# christmas-garland_easyeda.net
KiCad netlist of a schematic drawn in EasyEDA
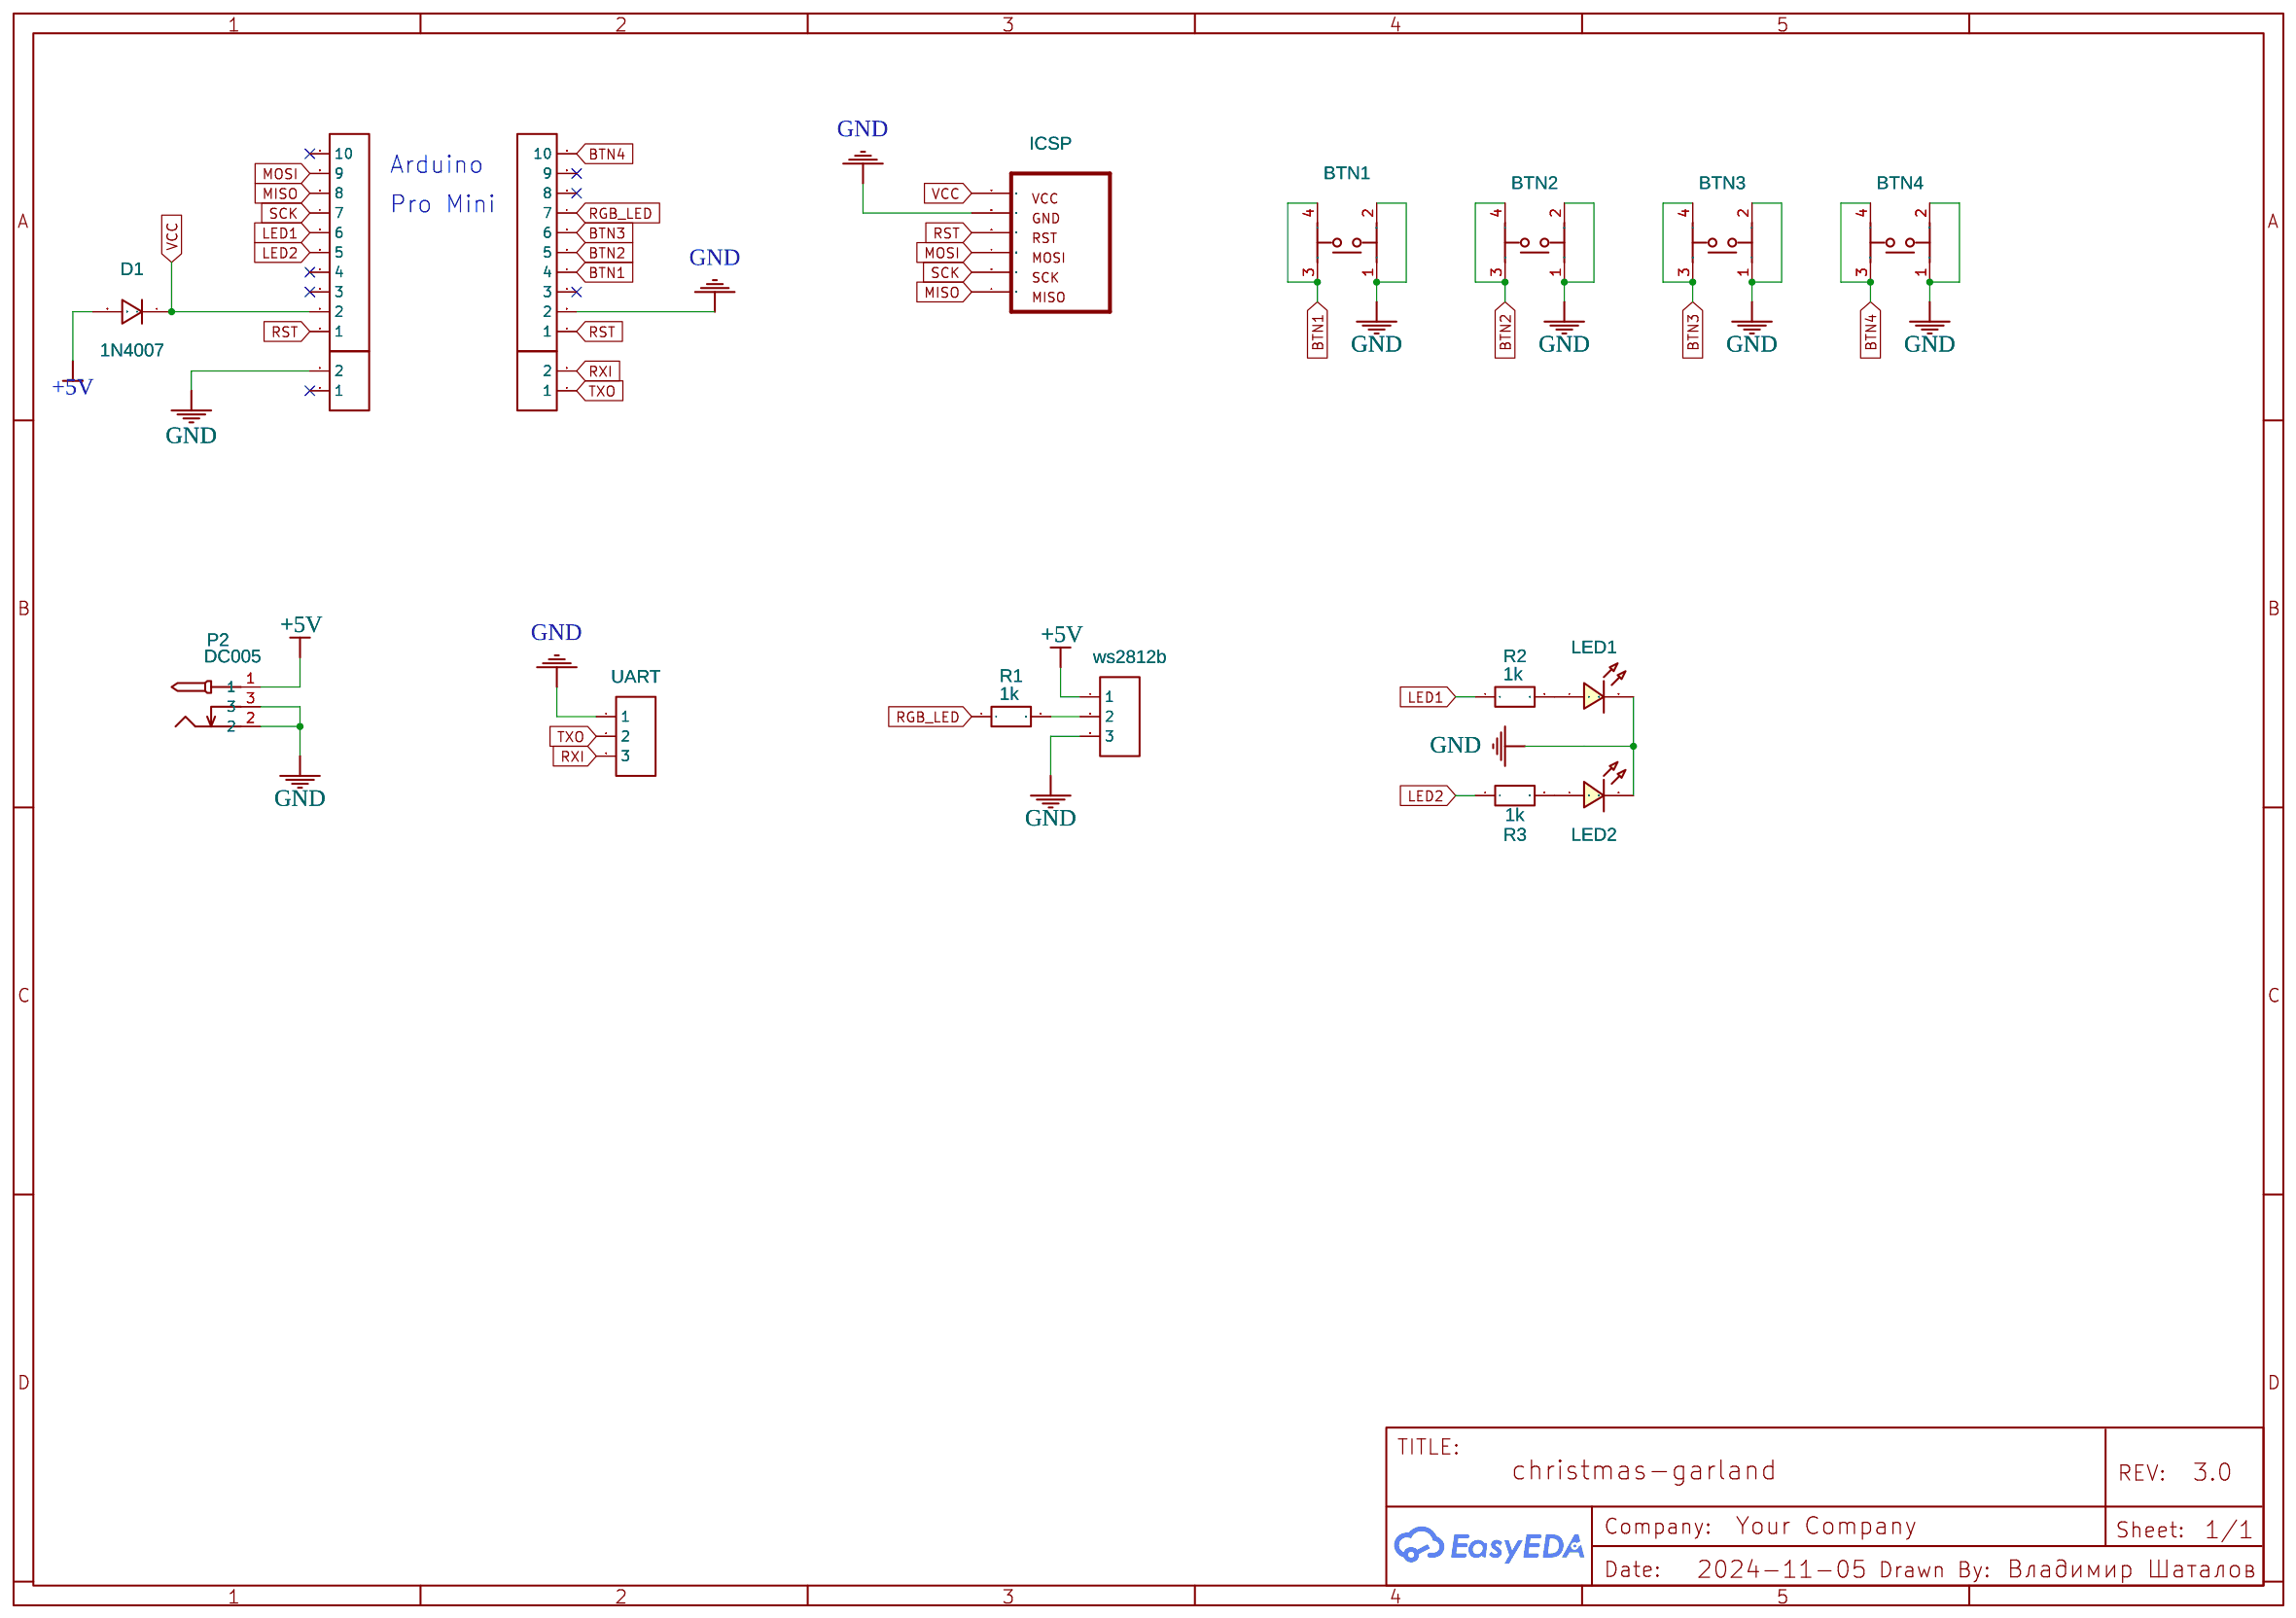
[diagram p0: schematic sheet]

(export (version "E")
  (design (tool "Eeschema 10.0.6"))
  (components
    (comp (ref "BTN1")
      (value "Reset")
      (fields (field (name "Manufacturer Part") "TS-1102-5016") (field (name "Manufacturer") "SOFNG"))
      (libsource (lib "") (part "SWITCH-6X6-5.08X7.62"))
    )
    (comp (ref "BTN2")
      (value "Reset")
      (fields (field (name "Manufacturer Part") "TS-1102-5016") (field (name "Manufacturer") "SOFNG"))
      (libsource (lib "") (part "SWITCH-6X6-5.08X7.62"))
    )
    (comp (ref "BTN3")
      (value "Reset")
      (fields (field (name "Manufacturer Part") "TS-1102-5016") (field (name "Manufacturer") "SOFNG"))
      (libsource (lib "") (part "SWITCH-6X6-5.08X7.62"))
    )
    (comp (ref "BTN4")
      (value "Reset")
      (fields (field (name "Manufacturer Part") "TS-1102-5016") (field (name "Manufacturer") "SOFNG"))
      (libsource (lib "") (part "SWITCH-6X6-5.08X7.62"))
    )
    (comp (ref "D1")
      (value "1N4007")
      (fields (field (name "Manufacturer Part") "1N4007W") (field (name "Manufacturer") "BLUE ROCKET"))
      (libsource (lib "") (part "1N4007W"))
    )
    (comp (ref "H1") (value "ws2812b") (libsource (lib "") (part "HDR-F-2.54_1x3")))
    (comp (ref "H2") (value "HDR-F-2.54_1x2") (libsource (lib "") (part "HDR-F-2.54_1x2")))
    (comp (ref "H3") (value "HDR-F-2.54_1x10") (libsource (lib "") (part "HDR-F-2.54_1x10")))
    (comp (ref "H4") (value "HDR-F-2.54_1x10") (libsource (lib "") (part "HDR-F-2.54_1x10_1")))
    (comp (ref "H5") (value "HDR-F-2.54_1x2") (libsource (lib "") (part "HDR-F-2.54_1x2_1")))
    (comp (ref "H6") (value "UART") (libsource (lib "") (part "HDR-F-2.54_1x3")))
    (comp (ref "ICSP") (value "SPI") (libsource (lib "") (part "PA_AVR_SPI_PROGRAMMER_ARDUINO")))
    (comp (ref "LED1")
      (value "LED-TH-3mm_G")
      (fields
        (field (name "Manufacturer Part") "204-10SYGD/S530-E3")
        (field (name "Manufacturer") "EVERLIGHT(台湾亿光)")
      )
      (libsource (lib "") (part "LED-TH-3mm_G"))
    )
    (comp (ref "LED2")
      (value "LED-TH-3mm_G")
      (fields
        (field (name "Manufacturer Part") "204-10SYGD/S530-E3")
        (field (name "Manufacturer") "EVERLIGHT(台湾亿光)")
      )
      (libsource (lib "") (part "LED-TH-3mm_G"))
    )
    (comp (ref "P2")
      (value "DC005")
      (fields
        (field (name "Manufacturer Part") "Three-pin power interface DC005 2.5MMsocket Bagged RHOS")
        (field (name "Manufacturer") "ReliaPro")
      )
      (libsource (lib "") (part "Three-pin power interface DC005 2.5MMsocket Bagged RHOS"))
    )
    (comp (ref "R1") (value "1k") (libsource (lib "") (part "R_0805_EU")))
    (comp (ref "R2") (value "1k") (libsource (lib "") (part "R_0805_EU")))
    (comp (ref "R3") (value "1k") (libsource (lib "") (part "R_0805_EU")))
  )
  (nets
    (net (code "1") (name "+5V") (class "Default")
      (node (ref "D1") (pin "2") (pinfunction "2_2") (pintype "unspecified"))
      (node (ref "H1") (pin "1") (pinfunction "1_1") (pintype "input"))
      (node (ref "P2") (pin "1") (pinfunction "1_1") (pintype "unspecified"))
    )
    (net (code "2") (name "BTN1") (class "Default")
      (node (ref "BTN1") (pin "3") (pinfunction "3_3") (pintype "unspecified"))
      (node (ref "BTN1") (pin "4") (pinfunction "4_4") (pintype "unspecified"))
      (node (ref "H4") (pin "4") (pinfunction "4_4") (pintype "unspecified"))
    )
    (net (code "3") (name "BTN2") (class "Default")
      (node (ref "BTN2") (pin "3") (pinfunction "3_3") (pintype "unspecified"))
      (node (ref "BTN2") (pin "4") (pinfunction "4_4") (pintype "unspecified"))
      (node (ref "H4") (pin "5") (pinfunction "5_5") (pintype "unspecified"))
    )
    (net (code "4") (name "BTN3") (class "Default")
      (node (ref "BTN3") (pin "3") (pinfunction "3_3") (pintype "unspecified"))
      (node (ref "BTN3") (pin "4") (pinfunction "4_4") (pintype "unspecified"))
      (node (ref "H4") (pin "6") (pinfunction "6_6") (pintype "unspecified"))
    )
    (net (code "5") (name "BTN4") (class "Default")
      (node (ref "BTN4") (pin "3") (pinfunction "3_3") (pintype "unspecified"))
      (node (ref "BTN4") (pin "4") (pinfunction "4_4") (pintype "unspecified"))
      (node (ref "H4") (pin "10") (pinfunction "10_10") (pintype "unspecified"))
    )
    (net (code "6") (name "GND") (class "Default")
      (node (ref "BTN1") (pin "1") (pinfunction "1_1") (pintype "unspecified"))
      (node (ref "BTN1") (pin "2") (pinfunction "2_2") (pintype "unspecified"))
      (node (ref "BTN2") (pin "1") (pinfunction "1_1") (pintype "unspecified"))
      (node (ref "BTN2") (pin "2") (pinfunction "2_2") (pintype "unspecified"))
      (node (ref "BTN3") (pin "1") (pinfunction "1_1") (pintype "unspecified"))
      (node (ref "BTN3") (pin "2") (pinfunction "2_2") (pintype "unspecified"))
      (node (ref "BTN4") (pin "1") (pinfunction "1_1") (pintype "unspecified"))
      (node (ref "BTN4") (pin "2") (pinfunction "2_2") (pintype "unspecified"))
      (node (ref "H1") (pin "3") (pinfunction "3_3") (pintype "input"))
      (node (ref "H2") (pin "2") (pinfunction "2_2") (pintype "input"))
      (node (ref "H4") (pin "2") (pinfunction "2_2") (pintype "unspecified"))
      (node (ref "H6") (pin "1") (pinfunction "1_1") (pintype "input"))
      (node (ref "ICSP") (pin "6") (pinfunction "GND_6") (pintype "unspecified"))
      (node (ref "LED1") (pin "2") (pinfunction "2_2") (pintype "unspecified"))
      (node (ref "LED2") (pin "2") (pinfunction "2_2") (pintype "unspecified"))
      (node (ref "P2") (pin "2") (pinfunction "2_2") (pintype "unspecified"))
      (node (ref "P2") (pin "3") (pinfunction "3_3") (pintype "unspecified"))
    )
    (net (code "7") (name "LED1") (class "Default")
      (node (ref "H3") (pin "6") (pinfunction "6_6") (pintype "unspecified"))
      (node (ref "R2") (pin "1") (pinfunction "1_1") (pintype "unspecified"))
    )
    (net (code "8") (name "LED2") (class "Default")
      (node (ref "H3") (pin "5") (pinfunction "5_5") (pintype "unspecified"))
      (node (ref "R3") (pin "1") (pinfunction "1_1") (pintype "unspecified"))
    )
    (net (code "9") (name "MISO") (class "Default")
      (node (ref "H3") (pin "8") (pinfunction "8_8") (pintype "unspecified"))
      (node (ref "ICSP") (pin "1") (pinfunction "MISO_1") (pintype "unspecified"))
    )
    (net (code "10") (name "MOSI") (class "Default")
      (node (ref "H3") (pin "9") (pinfunction "9_9") (pintype "unspecified"))
      (node (ref "ICSP") (pin "4") (pinfunction "MOSI_4") (pintype "unspecified"))
    )
    (net (code "11") (name "Net-(H1-Pad2)") (class "Default")
      (node (ref "H1") (pin "2") (pinfunction "2_2") (pintype "input"))
      (node (ref "R1") (pin "2") (pinfunction "2_2") (pintype "unspecified"))
    )
    (net (code "12") (name "Net-(LED1-Pad1)") (class "Default")
      (node (ref "LED1") (pin "1") (pinfunction "1_1") (pintype "unspecified"))
      (node (ref "R2") (pin "2") (pinfunction "2_2") (pintype "unspecified"))
    )
    (net (code "13") (name "Net-(LED2-Pad1)") (class "Default")
      (node (ref "LED2") (pin "1") (pinfunction "1_1") (pintype "unspecified"))
      (node (ref "R3") (pin "2") (pinfunction "2_2") (pintype "unspecified"))
    )
    (net (code "14") (name "RGB_LED") (class "Default")
      (node (ref "H4") (pin "7") (pinfunction "7_7") (pintype "unspecified"))
      (node (ref "R1") (pin "1") (pinfunction "1_1") (pintype "unspecified"))
    )
    (net (code "15") (name "RST") (class "Default")
      (node (ref "H3") (pin "1") (pinfunction "1_1") (pintype "unspecified"))
      (node (ref "H4") (pin "1") (pinfunction "1_1") (pintype "unspecified"))
      (node (ref "ICSP") (pin "5") (pinfunction "RST_5") (pintype "unspecified"))
    )
    (net (code "16") (name "RXI") (class "Default")
      (node (ref "H5") (pin "2") (pinfunction "2_2") (pintype "input"))
      (node (ref "H6") (pin "3") (pinfunction "3_3") (pintype "input"))
    )
    (net (code "17") (name "SCK") (class "Default")
      (node (ref "H3") (pin "7") (pinfunction "7_7") (pintype "unspecified"))
      (node (ref "ICSP") (pin "3") (pinfunction "SCK_3") (pintype "unspecified"))
    )
    (net (code "18") (name "TXO") (class "Default")
      (node (ref "H5") (pin "1") (pinfunction "1_1") (pintype "input"))
      (node (ref "H6") (pin "2") (pinfunction "2_2") (pintype "input"))
    )
    (net (code "19") (name "VCC") (class "Default")
      (node (ref "D1") (pin "1") (pinfunction "1_1") (pintype "unspecified"))
      (node (ref "H3") (pin "2") (pinfunction "2_2") (pintype "unspecified"))
      (node (ref "ICSP") (pin "2") (pinfunction "VCC_2") (pintype "unspecified"))
    )
    (net (code "20") (name "unconnected-(H2-Pad1)") (class "Default")
      (node (ref "H2") (pin "1") (pinfunction "1_1") (pintype "input+no_connect"))
    )
    (net (code "21") (name "unconnected-(H3-Pad3)") (class "Default")
      (node (ref "H3") (pin "3") (pinfunction "3_3") (pintype "unspecified+no_connect"))
    )
    (net (code "22") (name "unconnected-(H3-Pad4)") (class "Default")
      (node (ref "H3") (pin "4") (pinfunction "4_4") (pintype "unspecified+no_connect"))
    )
    (net (code "23") (name "unconnected-(H3-Pad10)") (class "Default")
      (node (ref "H3") (pin "10") (pinfunction "10_10") (pintype "unspecified+no_connect"))
    )
    (net (code "24") (name "unconnected-(H4-Pad3)") (class "Default")
      (node (ref "H4") (pin "3") (pinfunction "3_3") (pintype "unspecified+no_connect"))
    )
    (net (code "25") (name "unconnected-(H4-Pad8)") (class "Default")
      (node (ref "H4") (pin "8") (pinfunction "8_8") (pintype "unspecified+no_connect"))
    )
    (net (code "26") (name "unconnected-(H4-Pad9)") (class "Default")
      (node (ref "H4") (pin "9") (pinfunction "9_9") (pintype "unspecified+no_connect"))
    )
  )
)
